# FPGA_VCC.net
KiCad netlist of a schematic drawn in Altium Designer
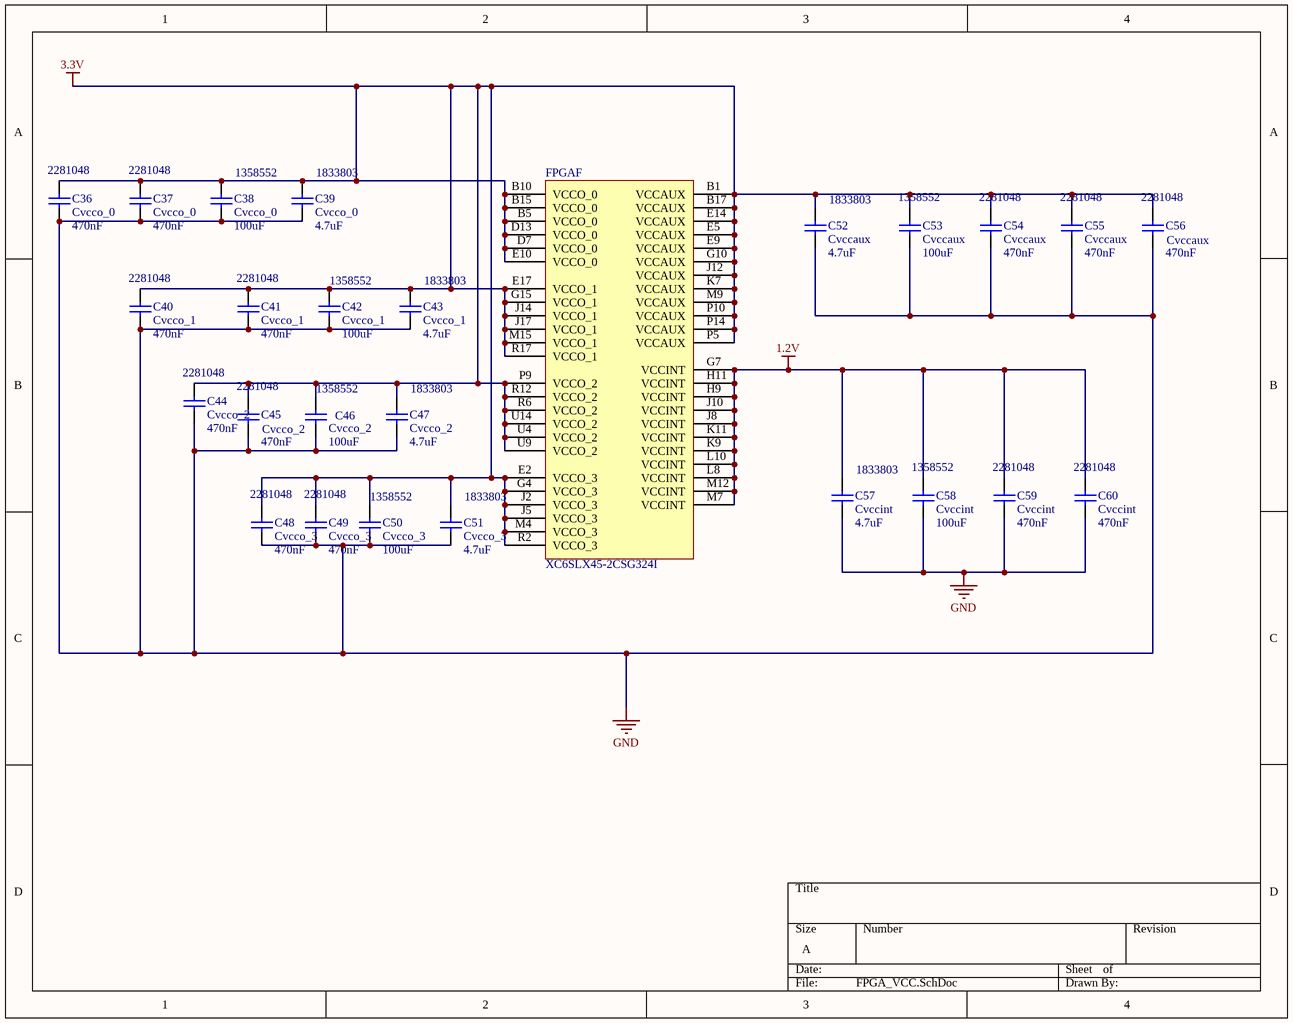
[diagram p0: FPGA_VCC.SchDoc]

(export (version "E")
  (design (tool "Eeschema 10.0.6"))
  (components
    (comp (ref "C36")
      (value "Cvcco_0")
      (footprint "C1206")
      (description "Capacitor (Semiconductor SIM Model)")
      (fields
        (field (name "ALTIUM_VALUE") "470nF")
        (field (name "SUPPLIER PART NUMBER 1") "2281048")
        (field (name "MANUFACTURER") "AVX")
        (field (name "MANUFACTURER PART NUMBER") "12061C474KAT2A")
        (field (name "PUBLISHER") "Altium Limited")
      )
      (libsource (lib "Miscellaneous Devices") (part "Cap Semi"))
    )
    (comp (ref "C37")
      (value "Cvcco_0")
      (footprint "C1206")
      (description "Capacitor (Semiconductor SIM Model)")
      (fields
        (field (name "ALTIUM_VALUE") "470nF")
        (field (name "SUPPLIER PART NUMBER 1") "2281048")
        (field (name "MANUFACTURER") "AVX")
        (field (name "MANUFACTURER PART NUMBER") "12061C474KAT2A")
        (field (name "PUBLISHER") "Altium Limited")
      )
      (libsource (lib "Miscellaneous Devices") (part "Cap Semi"))
    )
    (comp (ref "C38")
      (value "Cvcco_0")
      (footprint "C1206")
      (description "Capacitor (Semiconductor SIM Model)")
      (fields
        (field (name "ALTIUM_VALUE") "100uF")
        (field (name "SUPPLIER PART NUMBER 1") "1358552")
        (field (name "MANUFACTURER") "KEMET")
        (field (name "MANUFACTURER PART NUMBER") "C1206C107M9PACTU")
        (field (name "PUBLISHER") "Altium Limited")
      )
      (libsource (lib "Miscellaneous Devices") (part "Cap Semi"))
    )
    (comp (ref "C39")
      (value "Cvcco_0")
      (footprint "C1206")
      (description "Capacitor (Semiconductor SIM Model)")
      (fields
        (field (name "ALTIUM_VALUE") "4.7uF")
        (field (name "SUPPLIER PART NUMBER 1") "1833803")
        (field (name "MANUFACTURER") "AVX")
        (field (name "MANUFACTURER PART NUMBER") "06036D475KAT2A")
        (field (name "PUBLISHER") "Altium Limited")
      )
      (libsource (lib "Miscellaneous Devices") (part "Cap Semi"))
    )
    (comp (ref "C40")
      (value "Cvcco_1")
      (footprint "C1206")
      (description "Capacitor (Semiconductor SIM Model)")
      (fields
        (field (name "ALTIUM_VALUE") "470nF")
        (field (name "SUPPLIER PART NUMBER 1") "2281048")
        (field (name "MANUFACTURER") "AVX")
        (field (name "MANUFACTURER PART NUMBER") "12061C474KAT2A")
        (field (name "PUBLISHER") "Altium Limited")
      )
      (libsource (lib "Miscellaneous Devices") (part "Cap Semi"))
    )
    (comp (ref "C41")
      (value "Cvcco_1")
      (footprint "C1206")
      (description "Capacitor (Semiconductor SIM Model)")
      (fields
        (field (name "ALTIUM_VALUE") "470nF")
        (field (name "SUPPLIER PART NUMBER 1") "2281048")
        (field (name "MANUFACTURER") "AVX")
        (field (name "MANUFACTURER PART NUMBER") "12061C474KAT2A")
        (field (name "PUBLISHER") "Altium Limited")
      )
      (libsource (lib "Miscellaneous Devices") (part "Cap Semi"))
    )
    (comp (ref "C42")
      (value "Cvcco_1")
      (footprint "C1206")
      (description "Capacitor (Semiconductor SIM Model)")
      (fields
        (field (name "ALTIUM_VALUE") "100uF")
        (field (name "SUPPLIER PART NUMBER 1") "1358552")
        (field (name "MANUFACTURER") "KEMET")
        (field (name "MANUFACTURER PART NUMBER") "C1206C107M9PACTU")
        (field (name "PUBLISHER") "Altium Limited")
      )
      (libsource (lib "Miscellaneous Devices") (part "Cap Semi"))
    )
    (comp (ref "C43")
      (value "Cvcco_1")
      (footprint "C1206")
      (description "Capacitor (Semiconductor SIM Model)")
      (fields
        (field (name "ALTIUM_VALUE") "4.7uF")
        (field (name "SUPPLIER PART NUMBER 1") "1833803")
        (field (name "MANUFACTURER") "AVX")
        (field (name "MANUFACTURER PART NUMBER") "06036D475KAT2A")
        (field (name "PUBLISHER") "Altium Limited")
      )
      (libsource (lib "Miscellaneous Devices") (part "Cap Semi"))
    )
    (comp (ref "C44")
      (value "Cvcco_2")
      (footprint "C1206")
      (description "Capacitor (Semiconductor SIM Model)")
      (fields
        (field (name "ALTIUM_VALUE") "470nF")
        (field (name "SUPPLIER PART NUMBER 1") "2281048")
        (field (name "MANUFACTURER") "AVX")
        (field (name "MANUFACTURER PART NUMBER") "12061C474KAT2A")
        (field (name "PUBLISHER") "Altium Limited")
      )
      (libsource (lib "Miscellaneous Devices") (part "Cap Semi"))
    )
    (comp (ref "C45")
      (value "Cvcco_2")
      (footprint "C1206")
      (description "Capacitor (Semiconductor SIM Model)")
      (fields
        (field (name "ALTIUM_VALUE") "470nF")
        (field (name "SUPPLIER PART NUMBER 1") "2281048")
        (field (name "MANUFACTURER") "AVX")
        (field (name "MANUFACTURER PART NUMBER") "12061C474KAT2A")
        (field (name "PUBLISHER") "Altium Limited")
      )
      (libsource (lib "Miscellaneous Devices") (part "Cap Semi"))
    )
    (comp (ref "C46")
      (value "Cvcco_2")
      (footprint "C1206")
      (description "Capacitor (Semiconductor SIM Model)")
      (fields
        (field (name "ALTIUM_VALUE") "100uF")
        (field (name "SUPPLIER PART NUMBER 1") "1358552")
        (field (name "MANUFACTURER") "KEMET")
        (field (name "MANUFACTURER PART NUMBER") "C1206C107M9PACTU")
        (field (name "PUBLISHER") "Altium Limited")
      )
      (libsource (lib "Miscellaneous Devices") (part "Cap Semi"))
    )
    (comp (ref "C47")
      (value "Cvcco_2")
      (footprint "C1206")
      (description "Capacitor (Semiconductor SIM Model)")
      (fields
        (field (name "ALTIUM_VALUE") "4.7uF")
        (field (name "SUPPLIER PART NUMBER 1") "1833803")
        (field (name "MANUFACTURER") "AVX")
        (field (name "MANUFACTURER PART NUMBER") "06036D475KAT2A")
        (field (name "PUBLISHER") "Altium Limited")
      )
      (libsource (lib "Miscellaneous Devices") (part "Cap Semi"))
    )
    (comp (ref "C48")
      (value "Cvcco_3")
      (footprint "C1206")
      (description "Capacitor (Semiconductor SIM Model)")
      (fields
        (field (name "ALTIUM_VALUE") "470nF")
        (field (name "SUPPLIER PART NUMBER 1") "2281048")
        (field (name "MANUFACTURER") "AVX")
        (field (name "MANUFACTURER PART NUMBER") "12061C474KAT2A")
        (field (name "PUBLISHER") "Altium Limited")
      )
      (libsource (lib "Miscellaneous Devices") (part "Cap Semi"))
    )
    (comp (ref "C49")
      (value "Cvcco_3")
      (footprint "C1206")
      (description "Capacitor (Semiconductor SIM Model)")
      (fields
        (field (name "ALTIUM_VALUE") "470nF")
        (field (name "SUPPLIER PART NUMBER 1") "2281048")
        (field (name "MANUFACTURER") "AVX")
        (field (name "MANUFACTURER PART NUMBER") "12061C474KAT2A")
        (field (name "PUBLISHER") "Altium Limited")
      )
      (libsource (lib "Miscellaneous Devices") (part "Cap Semi"))
    )
    (comp (ref "C50")
      (value "Cvcco_3")
      (footprint "C1206")
      (description "Capacitor (Semiconductor SIM Model)")
      (fields
        (field (name "ALTIUM_VALUE") "100uF")
        (field (name "SUPPLIER PART NUMBER 1") "1358552")
        (field (name "MANUFACTURER") "KEMET")
        (field (name "MANUFACTURER PART NUMBER") "C1206C107M9PACTU")
        (field (name "PUBLISHER") "Altium Limited")
      )
      (libsource (lib "Miscellaneous Devices") (part "Cap Semi"))
    )
    (comp (ref "C51")
      (value "Cvcco_3")
      (footprint "C1206")
      (description "Capacitor (Semiconductor SIM Model)")
      (fields
        (field (name "ALTIUM_VALUE") "4.7uF")
        (field (name "SUPPLIER PART NUMBER 1") "1833803")
        (field (name "MANUFACTURER") "AVX")
        (field (name "MANUFACTURER PART NUMBER") "06036D475KAT2A")
        (field (name "PUBLISHER") "Altium Limited")
      )
      (libsource (lib "Miscellaneous Devices") (part "Cap Semi"))
    )
    (comp (ref "C52")
      (value "Cvccaux")
      (footprint "C1206")
      (description "Capacitor (Semiconductor SIM Model)")
      (fields
        (field (name "ALTIUM_VALUE") "4.7uF")
        (field (name "SUPPLIER PART NUMBER 1") "1833803")
        (field (name "MANUFACTURER") "AVX")
        (field (name "MANUFACTURER PART NUMBER") "06036D475KAT2A")
        (field (name "PUBLISHER") "Altium Limited")
      )
      (libsource (lib "Miscellaneous Devices") (part "Cap Semi"))
    )
    (comp (ref "C53")
      (value "Cvccaux")
      (footprint "C1206")
      (description "Capacitor (Semiconductor SIM Model)")
      (fields
        (field (name "ALTIUM_VALUE") "100uF")
        (field (name "SUPPLIER PART NUMBER 1") "1358552")
        (field (name "MANUFACTURER") "KEMET")
        (field (name "MANUFACTURER PART NUMBER") "C1206C107M9PACTU")
        (field (name "PUBLISHER") "Altium Limited")
      )
      (libsource (lib "Miscellaneous Devices") (part "Cap Semi"))
    )
    (comp (ref "C54")
      (value "Cvccaux")
      (footprint "C1206")
      (description "Capacitor (Semiconductor SIM Model)")
      (fields
        (field (name "ALTIUM_VALUE") "470nF")
        (field (name "SUPPLIER PART NUMBER 1") "2281048")
        (field (name "MANUFACTURER") "AVX")
        (field (name "MANUFACTURER PART NUMBER") "12061C474KAT2A")
        (field (name "PUBLISHER") "Altium Limited")
      )
      (libsource (lib "Miscellaneous Devices") (part "Cap Semi"))
    )
    (comp (ref "C55")
      (value "Cvccaux")
      (footprint "C1206")
      (description "Capacitor (Semiconductor SIM Model)")
      (fields
        (field (name "ALTIUM_VALUE") "470nF")
        (field (name "SUPPLIER PART NUMBER 1") "2281048")
        (field (name "MANUFACTURER") "AVX")
        (field (name "MANUFACTURER PART NUMBER") "12061C474KAT2A")
        (field (name "PUBLISHER") "Altium Limited")
      )
      (libsource (lib "Miscellaneous Devices") (part "Cap Semi"))
    )
    (comp (ref "C56")
      (value "Cvccaux")
      (footprint "C1206")
      (description "Capacitor (Semiconductor SIM Model)")
      (fields
        (field (name "ALTIUM_VALUE") "470nF")
        (field (name "SUPPLIER PART NUMBER 1") "2281048")
        (field (name "MANUFACTURER") "AVX")
        (field (name "MANUFACTURER PART NUMBER") "12061C474KAT2A")
        (field (name "PUBLISHER") "Altium Limited")
      )
      (libsource (lib "Miscellaneous Devices") (part "Cap Semi"))
    )
    (comp (ref "C57")
      (value "Cvccint")
      (footprint "C1206")
      (description "Capacitor (Semiconductor SIM Model)")
      (fields
        (field (name "ALTIUM_VALUE") "4.7uF")
        (field (name "SUPPLIER PART NUMBER 1") "1833803")
        (field (name "MANUFACTURER") "AVX")
        (field (name "MANUFACTURER PART NUMBER") "06036D475KAT2A")
        (field (name "PUBLISHER") "Altium Limited")
      )
      (libsource (lib "Miscellaneous Devices") (part "Cap Semi"))
    )
    (comp (ref "C58")
      (value "Cvccint")
      (footprint "C1206")
      (description "Capacitor (Semiconductor SIM Model)")
      (fields
        (field (name "ALTIUM_VALUE") "100uF")
        (field (name "SUPPLIER PART NUMBER 1") "1358552")
        (field (name "MANUFACTURER") "KEMET")
        (field (name "MANUFACTURER PART NUMBER") "C1206C107M9PACTU")
        (field (name "PUBLISHER") "Altium Limited")
      )
      (libsource (lib "Miscellaneous Devices") (part "Cap Semi"))
    )
    (comp (ref "C59")
      (value "Cvccint")
      (footprint "C1206")
      (description "Capacitor (Semiconductor SIM Model)")
      (fields
        (field (name "ALTIUM_VALUE") "470nF")
        (field (name "SUPPLIER PART NUMBER 1") "2281048")
        (field (name "MANUFACTURER") "AVX")
        (field (name "MANUFACTURER PART NUMBER") "12061C474KAT2A")
        (field (name "PUBLISHER") "Altium Limited")
      )
      (libsource (lib "Miscellaneous Devices") (part "Cap Semi"))
    )
    (comp (ref "C60")
      (value "Cvccint")
      (footprint "C1206")
      (description "Capacitor (Semiconductor SIM Model)")
      (fields
        (field (name "ALTIUM_VALUE") "470nF")
        (field (name "SUPPLIER PART NUMBER 1") "2281048")
        (field (name "MANUFACTURER") "AVX")
        (field (name "MANUFACTURER PART NUMBER") "12061C474KAT2A")
        (field (name "PUBLISHER") "Altium Limited")
      )
      (libsource (lib "Miscellaneous Devices") (part "Cap Semi"))
    )
    (comp (ref "FPGA")
      (value "XC6SLX45-2CSG324I")
      (footprint "CSG324")
      (libsource (lib "Altium Content Vault") (part "CMP-0067-00402-1"))
    )
  )
  (nets
    (net (code "1") (name "1.2V") (class "Default")
      (node (ref "C57") (pin "2") (pinfunction "2_2") (pintype "passive"))
      (node (ref "C58") (pin "2") (pinfunction "2_2") (pintype "passive"))
      (node (ref "C59") (pin "1") (pinfunction "1_1") (pintype "passive"))
      (node (ref "C60") (pin "1") (pinfunction "1_1") (pintype "passive"))
      (node (ref "FPGA") (pin "G7") (pinfunction "VCCINT_G7") (pintype "power_in"))
      (node (ref "FPGA") (pin "H11") (pinfunction "VCCINT_H11") (pintype "power_in"))
      (node (ref "FPGA") (pin "H9") (pinfunction "VCCINT_H9") (pintype "power_in"))
      (node (ref "FPGA") (pin "J10") (pinfunction "VCCINT_J10") (pintype "power_in"))
      (node (ref "FPGA") (pin "J8") (pinfunction "VCCINT_J8") (pintype "power_in"))
      (node (ref "FPGA") (pin "K11") (pinfunction "VCCINT_K11") (pintype "power_in"))
      (node (ref "FPGA") (pin "K9") (pinfunction "VCCINT_K9") (pintype "power_in"))
      (node (ref "FPGA") (pin "L10") (pinfunction "VCCINT_L10") (pintype "power_in"))
      (node (ref "FPGA") (pin "L8") (pinfunction "VCCINT_L8") (pintype "power_in"))
      (node (ref "FPGA") (pin "M12") (pinfunction "VCCINT_M12") (pintype "power_in"))
      (node (ref "FPGA") (pin "M7") (pinfunction "VCCINT_M7") (pintype "power_in"))
    )
    (net (code "2") (name "3.3V") (class "Default")
      (node (ref "C36") (pin "1") (pinfunction "1_1") (pintype "passive"))
      (node (ref "C37") (pin "1") (pinfunction "1_1") (pintype "passive"))
      (node (ref "C38") (pin "2") (pinfunction "2_2") (pintype "passive"))
      (node (ref "C39") (pin "2") (pinfunction "2_2") (pintype "passive"))
      (node (ref "C40") (pin "1") (pinfunction "1_1") (pintype "passive"))
      (node (ref "C41") (pin "1") (pinfunction "1_1") (pintype "passive"))
      (node (ref "C42") (pin "1") (pinfunction "1_1") (pintype "passive"))
      (node (ref "C43") (pin "2") (pinfunction "2_2") (pintype "passive"))
      (node (ref "C44") (pin "1") (pinfunction "1_1") (pintype "passive"))
      (node (ref "C45") (pin "1") (pinfunction "1_1") (pintype "passive"))
      (node (ref "C46") (pin "2") (pinfunction "2_2") (pintype "passive"))
      (node (ref "C47") (pin "2") (pinfunction "2_2") (pintype "passive"))
      (node (ref "C48") (pin "1") (pinfunction "1_1") (pintype "passive"))
      (node (ref "C49") (pin "1") (pinfunction "1_1") (pintype "passive"))
      (node (ref "C50") (pin "2") (pinfunction "2_2") (pintype "passive"))
      (node (ref "C51") (pin "2") (pinfunction "2_2") (pintype "passive"))
      (node (ref "C52") (pin "2") (pinfunction "2_2") (pintype "passive"))
      (node (ref "C53") (pin "2") (pinfunction "2_2") (pintype "passive"))
      (node (ref "C54") (pin "1") (pinfunction "1_1") (pintype "passive"))
      (node (ref "C55") (pin "1") (pinfunction "1_1") (pintype "passive"))
      (node (ref "C56") (pin "1") (pinfunction "1_1") (pintype "passive"))
      (node (ref "FPGA") (pin "B1") (pinfunction "VCCAUX_B1") (pintype "power_in"))
      (node (ref "FPGA") (pin "B10") (pinfunction "VCCO_0_B10") (pintype "power_in"))
      (node (ref "FPGA") (pin "B15") (pinfunction "VCCO_0_B15") (pintype "power_in"))
      (node (ref "FPGA") (pin "B17") (pinfunction "VCCAUX_B17") (pintype "power_in"))
      (node (ref "FPGA") (pin "B5") (pinfunction "VCCO_0_B5") (pintype "power_in"))
      (node (ref "FPGA") (pin "D13") (pinfunction "VCCO_0_D13") (pintype "power_in"))
      (node (ref "FPGA") (pin "D7") (pinfunction "VCCO_0_D7") (pintype "power_in"))
      (node (ref "FPGA") (pin "E10") (pinfunction "VCCO_0_E10") (pintype "power_in"))
      (node (ref "FPGA") (pin "E14") (pinfunction "VCCAUX_E14") (pintype "power_in"))
      (node (ref "FPGA") (pin "E17") (pinfunction "VCCO_1_E17") (pintype "power_in"))
      (node (ref "FPGA") (pin "E2") (pinfunction "VCCO_3_E2") (pintype "power_in"))
      (node (ref "FPGA") (pin "E5") (pinfunction "VCCAUX_E5") (pintype "power_in"))
      (node (ref "FPGA") (pin "E9") (pinfunction "VCCAUX_E9") (pintype "power_in"))
      (node (ref "FPGA") (pin "G10") (pinfunction "VCCAUX_G10") (pintype "power_in"))
      (node (ref "FPGA") (pin "G15") (pinfunction "VCCO_1_G15") (pintype "power_in"))
      (node (ref "FPGA") (pin "G4") (pinfunction "VCCO_3_G4") (pintype "power_in"))
      (node (ref "FPGA") (pin "J12") (pinfunction "VCCAUX_J12") (pintype "power_in"))
      (node (ref "FPGA") (pin "J14") (pinfunction "VCCO_1_J14") (pintype "power_in"))
      (node (ref "FPGA") (pin "J17") (pinfunction "VCCO_1_J17") (pintype "power_in"))
      (node (ref "FPGA") (pin "J2") (pinfunction "VCCO_3_J2") (pintype "power_in"))
      (node (ref "FPGA") (pin "J5") (pinfunction "VCCO_3_J5") (pintype "power_in"))
      (node (ref "FPGA") (pin "K7") (pinfunction "VCCAUX_K7") (pintype "power_in"))
      (node (ref "FPGA") (pin "M15") (pinfunction "VCCO_1_M15") (pintype "power_in"))
      (node (ref "FPGA") (pin "M4") (pinfunction "VCCO_3_M4") (pintype "power_in"))
      (node (ref "FPGA") (pin "M9") (pinfunction "VCCAUX_M9") (pintype "power_in"))
      (node (ref "FPGA") (pin "P10") (pinfunction "VCCAUX_P10") (pintype "power_in"))
      (node (ref "FPGA") (pin "P14") (pinfunction "VCCAUX_P14") (pintype "power_in"))
      (node (ref "FPGA") (pin "P5") (pinfunction "VCCAUX_P5") (pintype "power_in"))
      (node (ref "FPGA") (pin "P9") (pinfunction "VCCO_2_P9") (pintype "power_in"))
      (node (ref "FPGA") (pin "R12") (pinfunction "VCCO_2_R12") (pintype "power_in"))
      (node (ref "FPGA") (pin "R17") (pinfunction "VCCO_1_R17") (pintype "power_in"))
      (node (ref "FPGA") (pin "R2") (pinfunction "VCCO_3_R2") (pintype "power_in"))
      (node (ref "FPGA") (pin "R6") (pinfunction "VCCO_2_R6") (pintype "power_in"))
      (node (ref "FPGA") (pin "U14") (pinfunction "VCCO_2_U14") (pintype "power_in"))
      (node (ref "FPGA") (pin "U4") (pinfunction "VCCO_2_U4") (pintype "power_in"))
      (node (ref "FPGA") (pin "U9") (pinfunction "VCCO_2_U9") (pintype "power_in"))
    )
    (net (code "3") (name "GND") (class "Default")
      (node (ref "C36") (pin "2") (pinfunction "2_2") (pintype "passive"))
      (node (ref "C37") (pin "2") (pinfunction "2_2") (pintype "passive"))
      (node (ref "C38") (pin "1") (pinfunction "1_1") (pintype "passive"))
      (node (ref "C39") (pin "1") (pinfunction "1_1") (pintype "passive"))
      (node (ref "C40") (pin "2") (pinfunction "2_2") (pintype "passive"))
      (node (ref "C41") (pin "2") (pinfunction "2_2") (pintype "passive"))
      (node (ref "C42") (pin "2") (pinfunction "2_2") (pintype "passive"))
      (node (ref "C43") (pin "1") (pinfunction "1_1") (pintype "passive"))
      (node (ref "C44") (pin "2") (pinfunction "2_2") (pintype "passive"))
      (node (ref "C45") (pin "2") (pinfunction "2_2") (pintype "passive"))
      (node (ref "C46") (pin "1") (pinfunction "1_1") (pintype "passive"))
      (node (ref "C47") (pin "1") (pinfunction "1_1") (pintype "passive"))
      (node (ref "C48") (pin "2") (pinfunction "2_2") (pintype "passive"))
      (node (ref "C49") (pin "2") (pinfunction "2_2") (pintype "passive"))
      (node (ref "C50") (pin "1") (pinfunction "1_1") (pintype "passive"))
      (node (ref "C51") (pin "1") (pinfunction "1_1") (pintype "passive"))
      (node (ref "C52") (pin "1") (pinfunction "1_1") (pintype "passive"))
      (node (ref "C53") (pin "1") (pinfunction "1_1") (pintype "passive"))
      (node (ref "C54") (pin "2") (pinfunction "2_2") (pintype "passive"))
      (node (ref "C55") (pin "2") (pinfunction "2_2") (pintype "passive"))
      (node (ref "C56") (pin "2") (pinfunction "2_2") (pintype "passive"))
      (node (ref "C57") (pin "1") (pinfunction "1_1") (pintype "passive"))
      (node (ref "C58") (pin "1") (pinfunction "1_1") (pintype "passive"))
      (node (ref "C59") (pin "2") (pinfunction "2_2") (pintype "passive"))
      (node (ref "C60") (pin "2") (pinfunction "2_2") (pintype "passive"))
    )
  )
)
